# POWER_3.net
KiCad netlist of a schematic drawn in Altium Designer
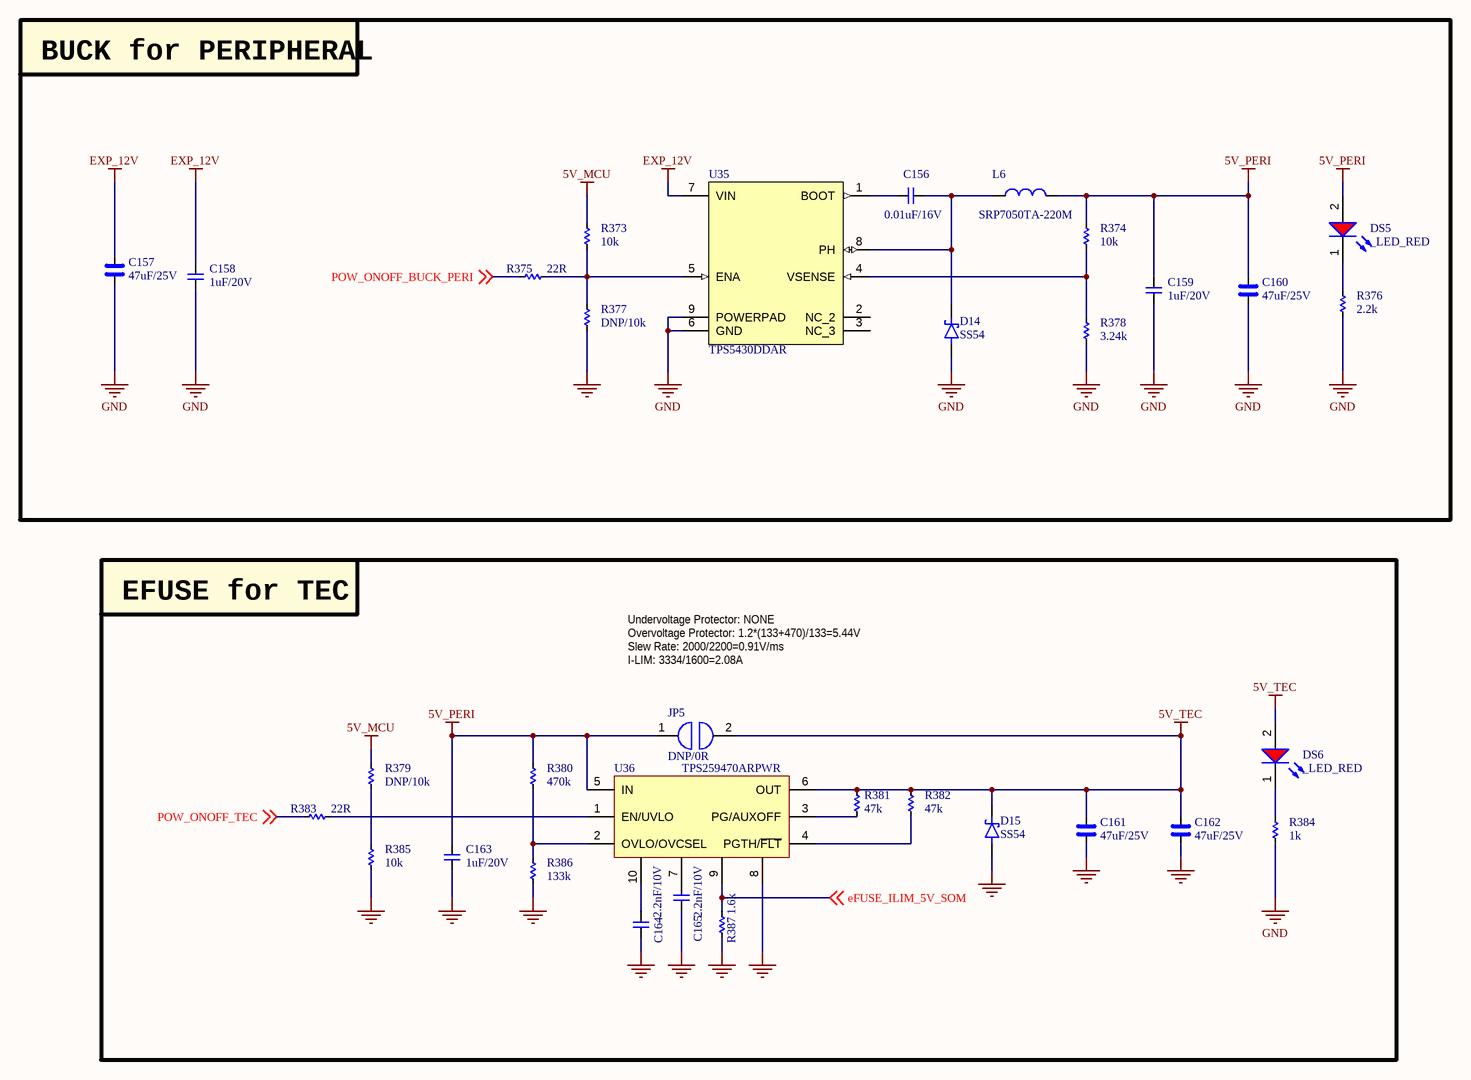
[diagram p0: POWER_3.SchDoc]

(export (version "E")
  (design (tool "Eeschema 10.0.6"))
  (components
    (comp (ref "C156")
      (value "0.01uF/16V")
      (footprint "CAP_C_1005X60")
      (description "CAP CHIP")
      (libsource (lib "LABLIB") (part "_CAP_C_2"))
    )
    (comp (ref "C157")
      (value "47uF/25V")
      (footprint "CAP_C_3225X80")
      (description "CAP CHIP High Value")
      (libsource (lib "LABLIB") (part "_CAP_C_High_2"))
    )
    (comp (ref "C158")
      (value "1uF/20V")
      (footprint "CAP_C_1005X60")
      (description "CAP CHIP")
      (libsource (lib "LABLIB") (part "_CAP_C_2"))
    )
    (comp (ref "C159")
      (value "1uF/20V")
      (footprint "CAP_C_1005X60")
      (description "CAP CHIP")
      (libsource (lib "LABLIB") (part "_CAP_C_2"))
    )
    (comp (ref "C160")
      (value "47uF/25V")
      (footprint "CAP_C_3225X80")
      (description "CAP CHIP High Value")
      (libsource (lib "LABLIB") (part "_CAP_C_High_2"))
    )
    (comp (ref "C161")
      (value "47uF/25V")
      (footprint "CAP_C_3225X80")
      (description "CAP CHIP High Value")
      (libsource (lib "LABLIB") (part "_CAP_C_High_2"))
    )
    (comp (ref "C162")
      (value "47uF/25V")
      (footprint "CAP_C_3225X80")
      (description "CAP CHIP High Value")
      (libsource (lib "LABLIB") (part "_CAP_C_High_2"))
    )
    (comp (ref "C163")
      (value "1uF/20V")
      (footprint "CAP_C_1005X60")
      (description "CAP CHIP")
      (libsource (lib "LABLIB") (part "_CAP_C_2"))
    )
    (comp (ref "C164")
      (value "2.2nF/10V")
      (footprint "CAP_C_1005X60")
      (description "CAP CHIP")
      (libsource (lib "LABLIB") (part "_CAP_C_2"))
    )
    (comp (ref "C165")
      (value "2.2nF/10V")
      (footprint "CAP_C_1005X60")
      (description "CAP CHIP")
      (libsource (lib "LABLIB") (part "_CAP_C_2"))
    )
    (comp (ref "D14")
      (value "SS54")
      (footprint "DO-214AC_SMA")
      (description "DIODE SCHOTTKY")
      (libsource (lib "LABLIB") (part "DIODE SCHOTTKY"))
    )
    (comp (ref "D15")
      (value "SS54")
      (footprint "DO-214AC_SMA")
      (description "DIODE SCHOTTKY")
      (libsource (lib "LABLIB") (part "DIODE SCHOTTKY"))
    )
    (comp (ref "DS5") (value "_LED_RED") (footprint "LED_0402") (libsource (lib "LABLIB") (part "_LED_RED")))
    (comp (ref "DS6") (value "_LED_RED") (footprint "LED_0402") (libsource (lib "LABLIB") (part "_LED_RED")))
    (comp (ref "JP5") (value "DNP/0R") (footprint "RES_C_1608X60") (libsource (lib "EXP_V1") (part "JUMPER")))
    (comp (ref "L6")
      (value "SRP7050TA-220M")
      (footprint "PSM6050")
      (description "FIXED IND 22UH 2.5A 170 MOHM SMD")
      (libsource (lib "LABLIB") (part "SRP7050TA-220M"))
    )
    (comp (ref "R373")
      (value "10k")
      (footprint "RES_C_1005X40")
      (description "RES")
      (libsource (lib "LABLIB") (part "_RES_B_2"))
    )
    (comp (ref "R374")
      (value "10k")
      (footprint "RES_C_1005X40")
      (description "RES")
      (libsource (lib "LABLIB") (part "_RES_B_2"))
    )
    (comp (ref "R375")
      (value "22R")
      (footprint "RES_C_1005X40")
      (description "RES")
      (libsource (lib "LABLIB") (part "_RES_B_2"))
    )
    (comp (ref "R376")
      (value "2.2k")
      (footprint "RES_C_1005X40")
      (description "RES")
      (libsource (lib "LABLIB") (part "_RES_B_2"))
    )
    (comp (ref "R377")
      (value "DNP/10k")
      (footprint "RES_C_1005X40")
      (description "RES")
      (libsource (lib "LABLIB") (part "_RES_B_2"))
    )
    (comp (ref "R378")
      (value "3.24k")
      (footprint "RES_C_1005X40")
      (description "RES")
      (libsource (lib "LABLIB") (part "_RES_B_2"))
    )
    (comp (ref "R379")
      (value "DNP/10k")
      (footprint "RES_C_1005X40")
      (description "RES")
      (libsource (lib "LABLIB") (part "_RES_B_2"))
    )
    (comp (ref "R380")
      (value "470k")
      (footprint "RES_C_1005X40")
      (description "RES")
      (libsource (lib "LABLIB") (part "_RES_B_2"))
    )
    (comp (ref "R381")
      (value "47k")
      (footprint "RES_C_1005X40")
      (description "RES")
      (libsource (lib "LABLIB") (part "_RES_B_2"))
    )
    (comp (ref "R382")
      (value "47k")
      (footprint "RES_C_1005X40")
      (description "RES")
      (libsource (lib "LABLIB") (part "_RES_B_2"))
    )
    (comp (ref "R383")
      (value "22R")
      (footprint "RES_C_1005X40")
      (description "RES")
      (libsource (lib "LABLIB") (part "_RES_B_2"))
    )
    (comp (ref "R384")
      (value "1k")
      (footprint "RES_C_1005X40")
      (description "RES")
      (libsource (lib "LABLIB") (part "_RES_B_2"))
    )
    (comp (ref "R385")
      (value "10k")
      (footprint "RES_C_1005X40")
      (description "RES")
      (libsource (lib "LABLIB") (part "_RES_B_2"))
    )
    (comp (ref "R386")
      (value "133k")
      (footprint "RES_C_1005X40")
      (description "RES")
      (libsource (lib "LABLIB") (part "_RES_B_2"))
    )
    (comp (ref "R387")
      (value "1.6k")
      (footprint "RES_C_1005X40")
      (description "RES")
      (libsource (lib "LABLIB") (part "_RES_B_2"))
    )
    (comp (ref "U35")
      (value "TPS5430DDAR")
      (footprint "TPS5430DDAR_V3")
      (description "IC REG BUCK ADJ 3A 8SOPWR")
      (libsource (lib "EXP_HW_V3") (part "TPS5430DDAR"))
    )
    (comp (ref "U36")
      (value "TPS259470ARPWR")
      (footprint "VQFN-HR-10")
      (libsource (lib "EXP_HW_V3") (part "TPS259470ARPWR"))
    )
  )
  (nets
    (net (code "1") (name "5V_MCU") (class "Default")
      (node (ref "R373") (pin "1") (pinfunction "1_1") (pintype "passive"))
      (node (ref "R379") (pin "1") (pinfunction "1_1") (pintype "passive"))
    )
    (net (code "2") (name "5V_PERI") (class "Default")
      (node (ref "C159") (pin "2") (pinfunction "2_2") (pintype "passive"))
      (node (ref "C160") (pin "2") (pinfunction "2_2") (pintype "passive"))
      (node (ref "C163") (pin "2") (pinfunction "2_2") (pintype "passive"))
      (node (ref "DS5") (pin "2") (pinfunction "A_2") (pintype "passive"))
      (node (ref "JP5") (pin "1") (pinfunction "1_1") (pintype "passive"))
      (node (ref "L6") (pin "2") (pinfunction "2_2") (pintype "passive"))
      (node (ref "R374") (pin "2") (pinfunction "2_2") (pintype "passive"))
      (node (ref "R380") (pin "2") (pinfunction "2_2") (pintype "passive"))
      (node (ref "U36") (pin "5") (pinfunction "IN_5") (pintype "passive"))
    )
    (net (code "3") (name "5V_TEC") (class "Default")
      (node (ref "C161") (pin "2") (pinfunction "2_2") (pintype "passive"))
      (node (ref "C162") (pin "2") (pinfunction "2_2") (pintype "passive"))
      (node (ref "D15") (pin "1") (pinfunction "K_1") (pintype "passive"))
      (node (ref "DS6") (pin "2") (pinfunction "A_2") (pintype "passive"))
      (node (ref "JP5") (pin "2") (pinfunction "2_2") (pintype "passive"))
      (node (ref "R381") (pin "2") (pinfunction "2_2") (pintype "passive"))
      (node (ref "R382") (pin "2") (pinfunction "2_2") (pintype "passive"))
      (node (ref "U36") (pin "6") (pinfunction "OUT_6") (pintype "passive"))
    )
    (net (code "4") (name "EXP_12V") (class "Default")
      (node (ref "C157") (pin "2") (pinfunction "2_2") (pintype "passive"))
      (node (ref "C158") (pin "2") (pinfunction "2_2") (pintype "passive"))
      (node (ref "U35") (pin "7") (pinfunction "VIN_7") (pintype "power_in"))
    )
    (net (code "5") (name "GND") (class "Default")
      (node (ref "C157") (pin "1") (pinfunction "1_1") (pintype "passive"))
      (node (ref "C158") (pin "1") (pinfunction "1_1") (pintype "passive"))
      (node (ref "C159") (pin "1") (pinfunction "1_1") (pintype "passive"))
      (node (ref "C160") (pin "1") (pinfunction "1_1") (pintype "passive"))
      (node (ref "C161") (pin "1") (pinfunction "1_1") (pintype "passive"))
      (node (ref "C162") (pin "1") (pinfunction "1_1") (pintype "passive"))
      (node (ref "C163") (pin "1") (pinfunction "1_1") (pintype "passive"))
      (node (ref "C164") (pin "1") (pinfunction "1_1") (pintype "passive"))
      (node (ref "C165") (pin "1") (pinfunction "1_1") (pintype "passive"))
      (node (ref "D14") (pin "2") (pinfunction "A_2") (pintype "passive"))
      (node (ref "D15") (pin "2") (pinfunction "A_2") (pintype "passive"))
      (node (ref "R376") (pin "1") (pinfunction "1_1") (pintype "passive"))
      (node (ref "R377") (pin "2") (pinfunction "2_2") (pintype "passive"))
      (node (ref "R378") (pin "1") (pinfunction "1_1") (pintype "passive"))
      (node (ref "R384") (pin "1") (pinfunction "1_1") (pintype "passive"))
      (node (ref "R385") (pin "2") (pinfunction "2_2") (pintype "passive"))
      (node (ref "R386") (pin "1") (pinfunction "1_1") (pintype "passive"))
      (node (ref "R387") (pin "1") (pinfunction "1_1") (pintype "passive"))
      (node (ref "U35") (pin "6") (pinfunction "GND_6") (pintype "power_in"))
      (node (ref "U35") (pin "9") (pinfunction "POWERPAD_9") (pintype "power_in"))
      (node (ref "U36") (pin "8") (pinfunction "8_8") (pintype "passive"))
    )
    (net (code "6") (name "Net-(C164-Pad2)") (class "Default")
      (node (ref "C164") (pin "2") (pinfunction "2_2") (pintype "passive"))
      (node (ref "U36") (pin "10") (pinfunction "10_10") (pintype "passive"))
    )
    (net (code "7") (name "Net-(C165-Pad2)") (class "Default")
      (node (ref "C165") (pin "2") (pinfunction "2_2") (pintype "passive"))
      (node (ref "U36") (pin "7") (pinfunction "7_7") (pintype "passive"))
    )
    (net (code "8") (name "Net-(D14-K)") (class "Default")
      (node (ref "C156") (pin "1") (pinfunction "1_1") (pintype "passive"))
      (node (ref "D14") (pin "1") (pinfunction "K_1") (pintype "passive"))
      (node (ref "L6") (pin "1") (pinfunction "1_1") (pintype "passive"))
      (node (ref "U35") (pin "8") (pinfunction "PH_8") (pintype "bidirectional"))
    )
    (net (code "9") (name "Net-(DS5-K)") (class "Default")
      (node (ref "DS5") (pin "1") (pinfunction "K_1") (pintype "passive"))
      (node (ref "R376") (pin "2") (pinfunction "2_2") (pintype "passive"))
    )
    (net (code "10") (name "Net-(DS6-K)") (class "Default")
      (node (ref "DS6") (pin "1") (pinfunction "K_1") (pintype "passive"))
      (node (ref "R384") (pin "2") (pinfunction "2_2") (pintype "passive"))
    )
    (net (code "11") (name "Net-(R379-Pad2)") (class "Default")
      (node (ref "R379") (pin "2") (pinfunction "2_2") (pintype "passive"))
      (node (ref "R385") (pin "1") (pinfunction "1_1") (pintype "passive"))
    )
    (net (code "12") (name "Net-(U35-BOOT)") (class "Default")
      (node (ref "C156") (pin "2") (pinfunction "2_2") (pintype "passive"))
      (node (ref "U35") (pin "1") (pinfunction "BOOT_1") (pintype "output"))
    )
    (net (code "13") (name "Net-(U35-ENA)") (class "Default")
      (node (ref "R373") (pin "2") (pinfunction "2_2") (pintype "passive"))
      (node (ref "R375") (pin "1") (pinfunction "1_1") (pintype "passive"))
      (node (ref "R377") (pin "1") (pinfunction "1_1") (pintype "passive"))
      (node (ref "U35") (pin "5") (pinfunction "ENA_5") (pintype "input"))
    )
    (net (code "14") (name "Net-(U35-VSENSE)") (class "Default")
      (node (ref "R374") (pin "1") (pinfunction "1_1") (pintype "passive"))
      (node (ref "R378") (pin "2") (pinfunction "2_2") (pintype "passive"))
      (node (ref "U35") (pin "4") (pinfunction "VSENSE_4") (pintype "input"))
    )
    (net (code "15") (name "Net-(U36-EN{slash}UVLO)") (class "Default")
      (node (ref "R383") (pin "1") (pinfunction "1_1") (pintype "passive"))
      (node (ref "U36") (pin "1") (pinfunction "EN/UVLO_1") (pintype "passive"))
    )
    (net (code "16") (name "Net-(U36-OVLO{slash}OVCSEL)") (class "Default")
      (node (ref "R380") (pin "1") (pinfunction "1_1") (pintype "passive"))
      (node (ref "R386") (pin "2") (pinfunction "2_2") (pintype "passive"))
      (node (ref "U36") (pin "2") (pinfunction "OVLO/OVCSEL_2") (pintype "passive"))
    )
    (net (code "17") (name "Net-(U36-PGTH{slash}~{FLT})") (class "Default")
      (node (ref "R382") (pin "1") (pinfunction "1_1") (pintype "passive"))
      (node (ref "U36") (pin "4") (pinfunction "PGTH/~{FLT}_4") (pintype "passive"))
    )
    (net (code "18") (name "Net-(U36-PG{slash}AUXOFF)") (class "Default")
      (node (ref "R381") (pin "1") (pinfunction "1_1") (pintype "passive"))
      (node (ref "U36") (pin "3") (pinfunction "PG/AUXOFF_3") (pintype "passive"))
    )
    (net (code "19") (name "POW_ONOFF_BUCK_PERI") (class "Default")
      (node (ref "R375") (pin "2") (pinfunction "2_2") (pintype "passive"))
    )
    (net (code "20") (name "POW_ONOFF_TEC") (class "Default")
      (node (ref "R383") (pin "2") (pinfunction "2_2") (pintype "passive"))
    )
    (net (code "21") (name "eFUSE_ILIM_5V_SOM") (class "Default")
      (node (ref "R387") (pin "2") (pinfunction "2_2") (pintype "passive"))
      (node (ref "U36") (pin "9") (pinfunction "9_9") (pintype "passive"))
    )
    (net (code "22") (name "unconnected-(U35-NC_2-Pad2)") (class "Default")
      (node (ref "U35") (pin "2") (pinfunction "NC_2_2") (pintype "passive"))
    )
    (net (code "23") (name "unconnected-(U35-NC_3-Pad3)") (class "Default")
      (node (ref "U35") (pin "3") (pinfunction "NC_3_3") (pintype "passive"))
    )
  )
)
